# Dash.net
KiCad netlist of a schematic drawn in Altium Designer
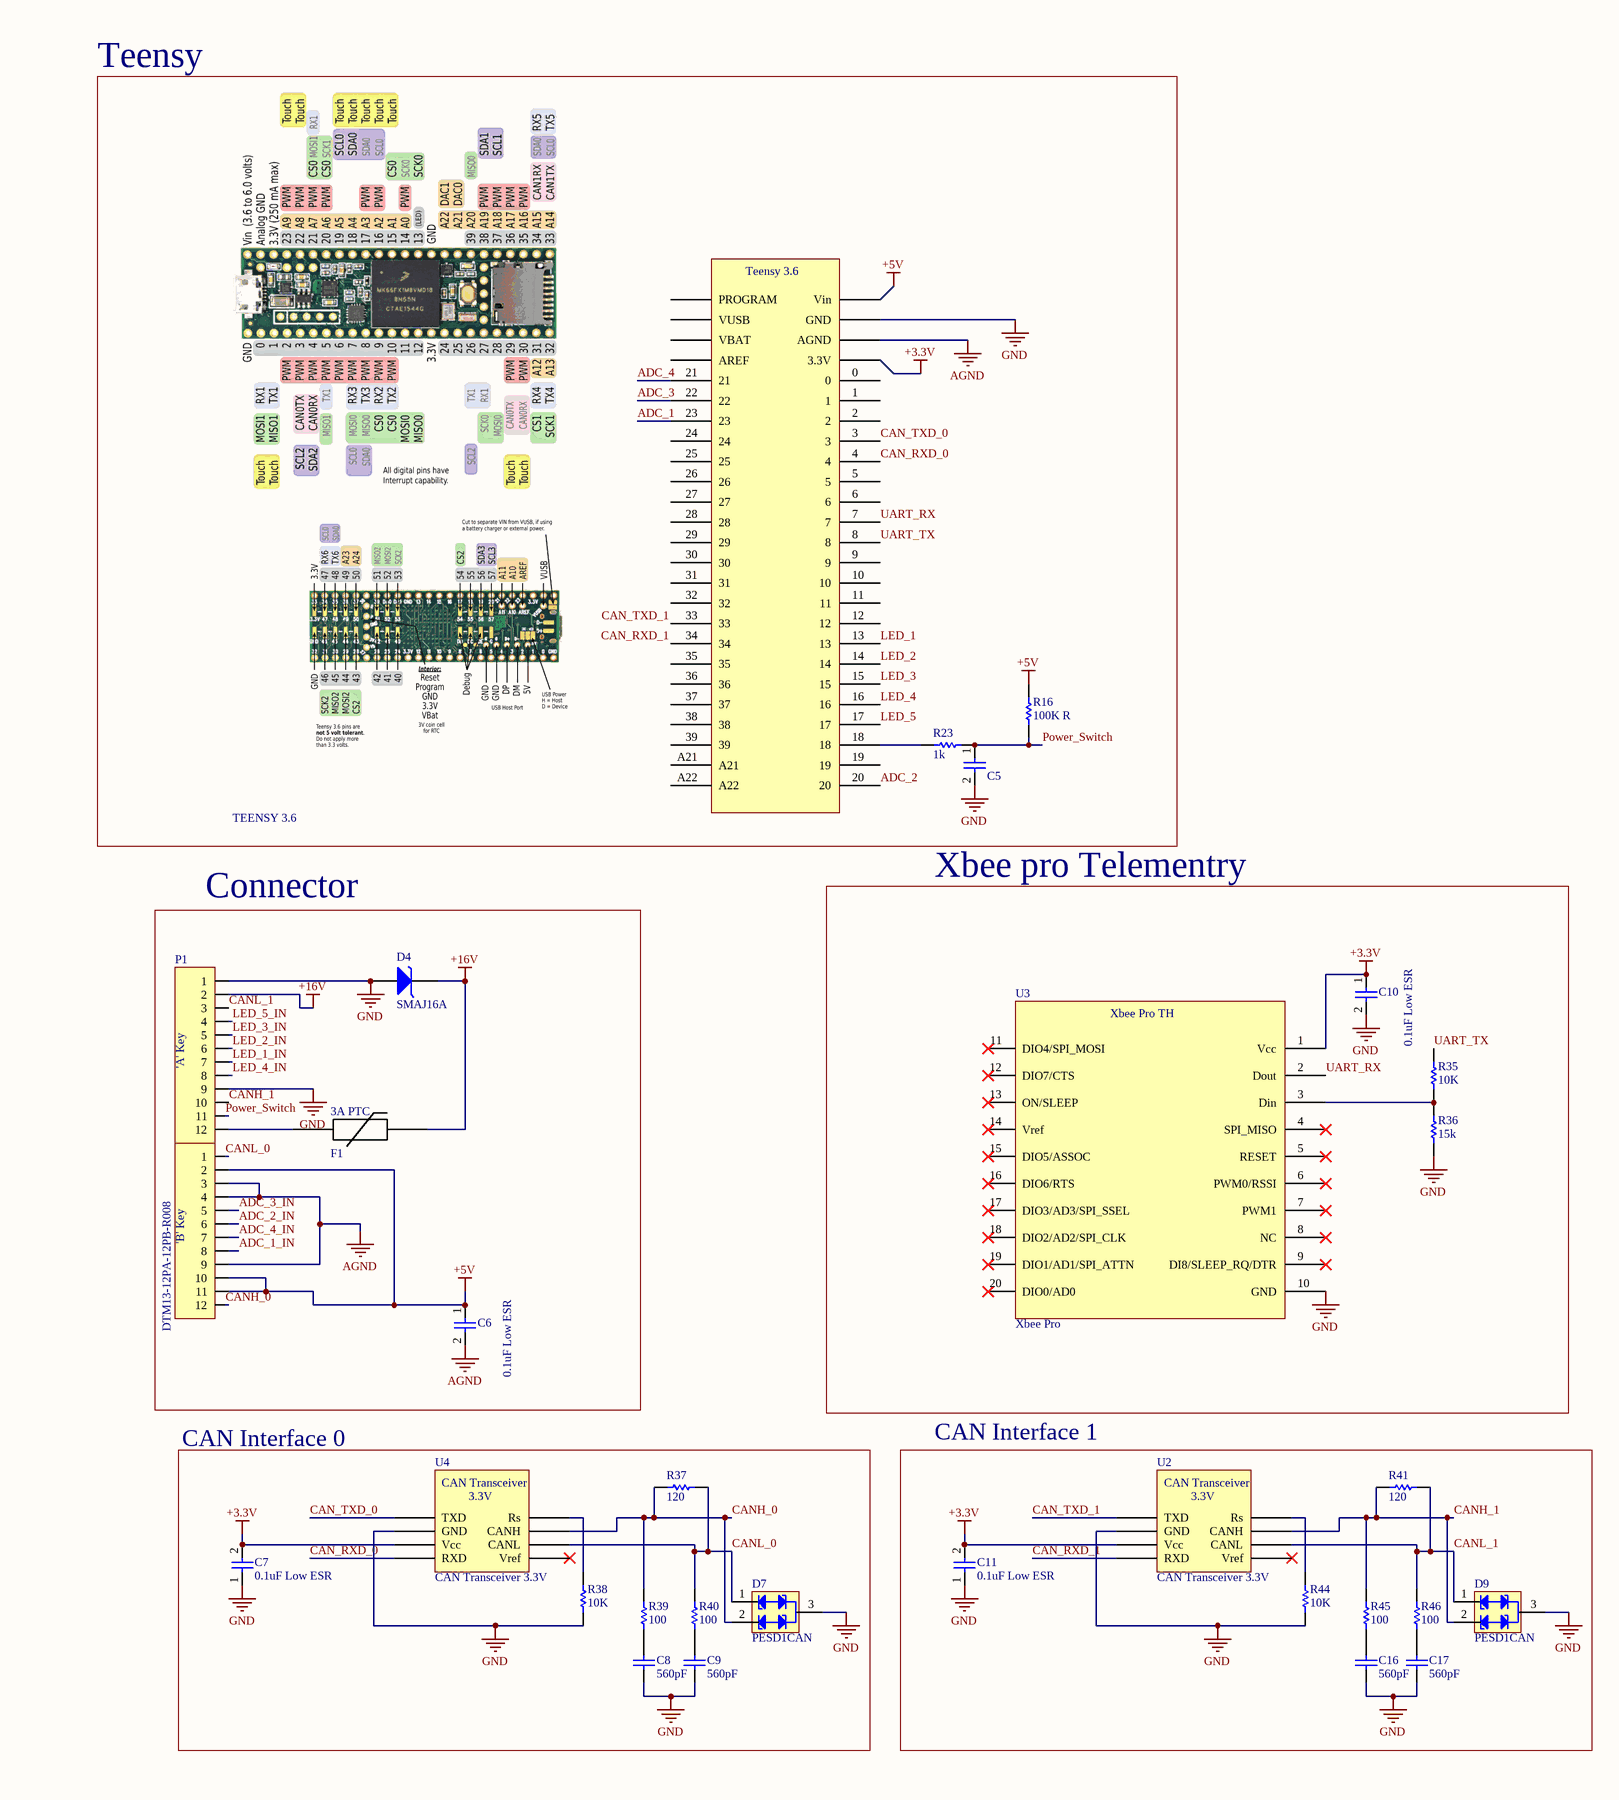
[diagram p0: Dash.SchDoc, left]
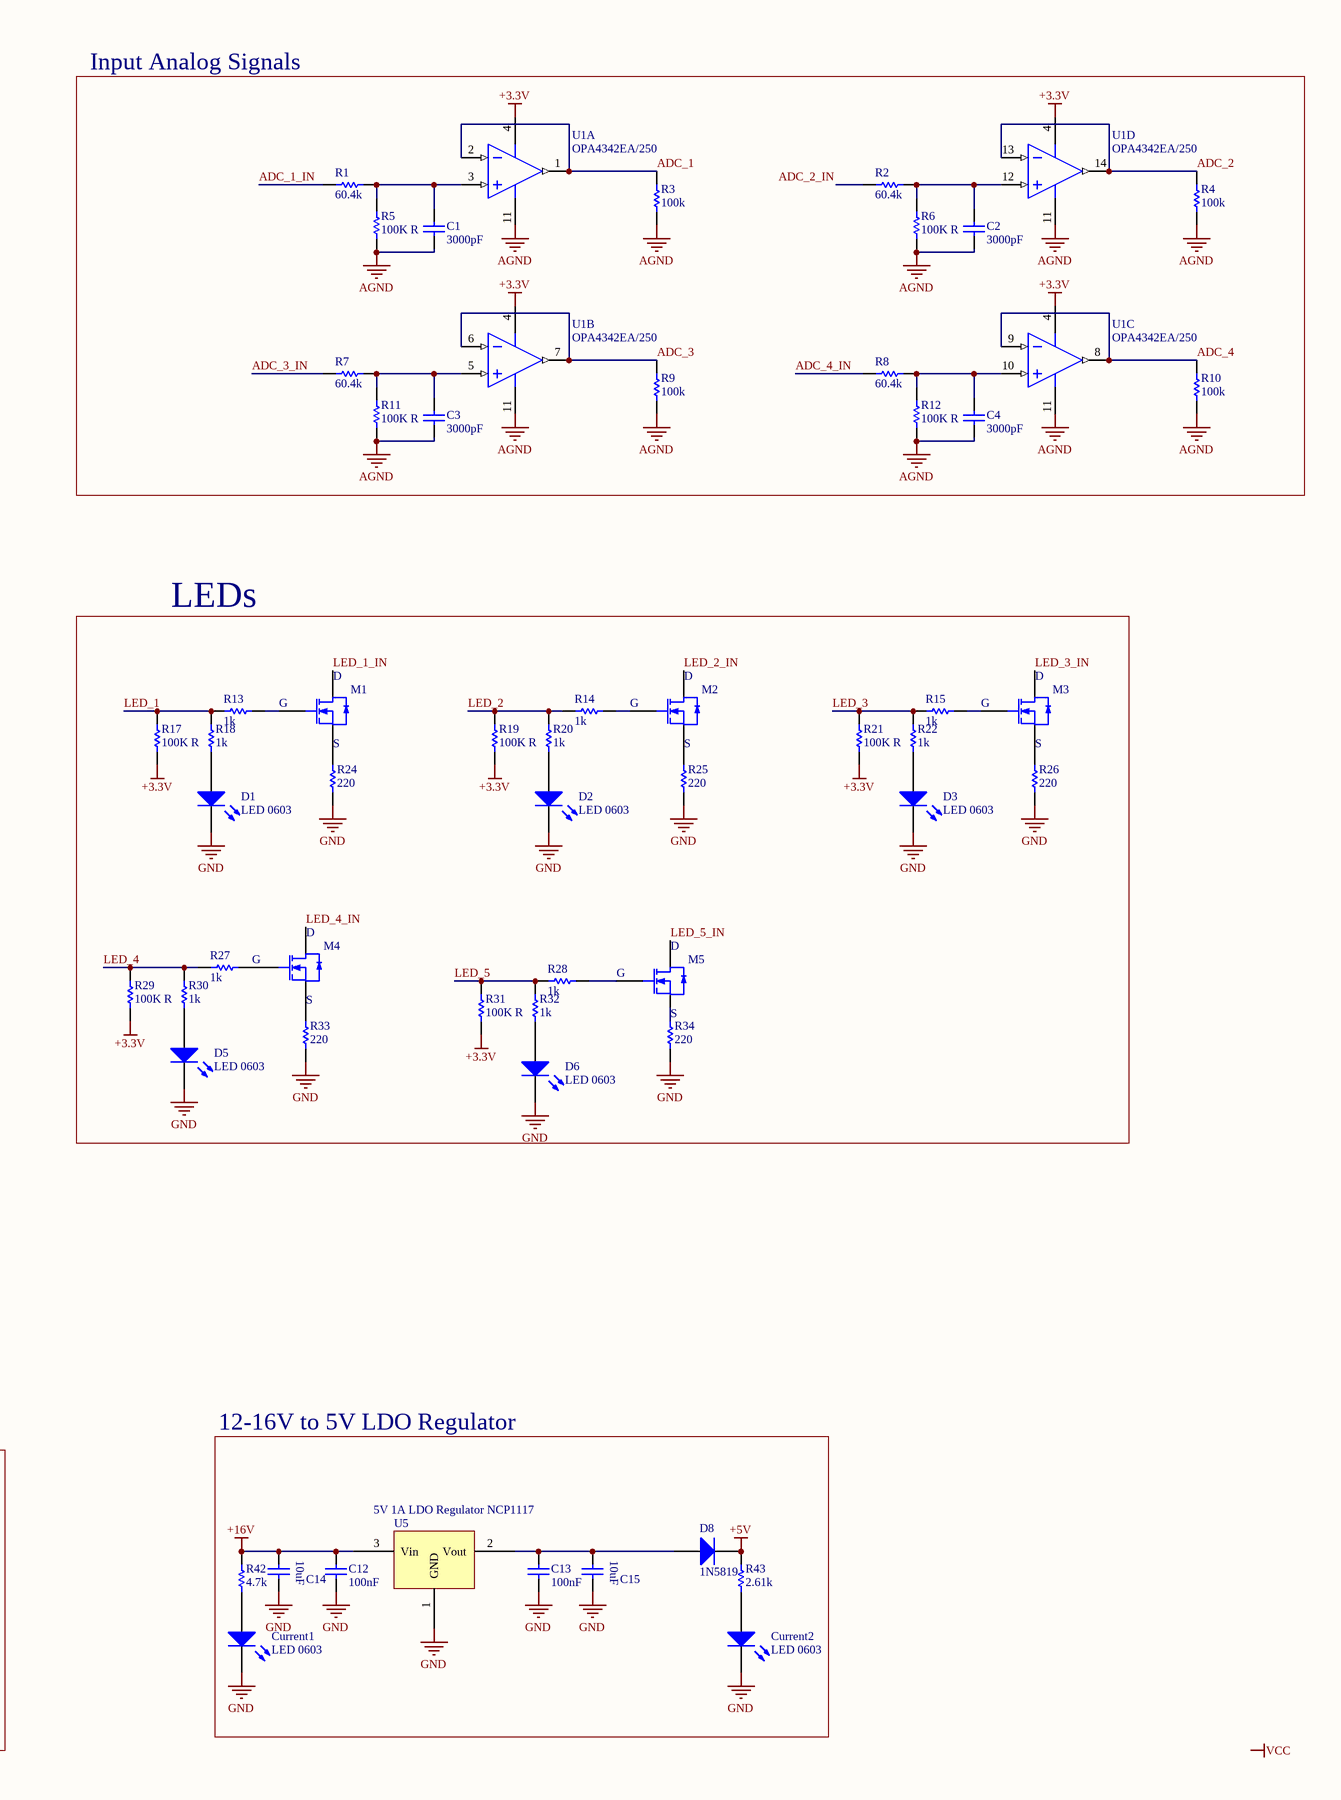
[diagram p1: Dash.SchDoc, right]

(export (version "E")
  (design (tool "Eeschema 10.0.6"))
  (components
    (comp (ref "C1")
      (value "C 3000pF")
      (footprint "DASH_PcbLib:J1-0603")
      (description "0603 Ceramic Capacitor")
      (fields
        (field (name "MANUFACTURER") "Murata Electronics North America")
        (field (name "MANUFACTURER PART NUMBER") "GRM1885C1H302JA01D")
        (field (name "CAPACITANCE") "3000pF")
      )
      (libsource (lib "BTPD_Schlib") (part "C 3000pF 0603 50V"))
    )
    (comp (ref "C2")
      (value "C 3000pF")
      (footprint "DASH_PcbLib:J1-0603")
      (description "0603 Ceramic Capacitor")
      (fields
        (field (name "MANUFACTURER") "Murata Electronics North America")
        (field (name "MANUFACTURER PART NUMBER") "GRM1885C1H302JA01D")
        (field (name "CAPACITANCE") "3000pF")
      )
      (libsource (lib "BTPD_Schlib") (part "C 3000pF 0603 50V"))
    )
    (comp (ref "C3")
      (value "C 3000pF")
      (footprint "DASH_PcbLib:J1-0603")
      (description "0603 Ceramic Capacitor")
      (fields
        (field (name "MANUFACTURER") "Murata Electronics North America")
        (field (name "MANUFACTURER PART NUMBER") "GRM1885C1H302JA01D")
        (field (name "CAPACITANCE") "3000pF")
      )
      (libsource (lib "BTPD_Schlib") (part "C 3000pF 0603 50V"))
    )
    (comp (ref "C4")
      (value "C 3000pF")
      (footprint "DASH_PcbLib:J1-0603")
      (description "0603 Ceramic Capacitor")
      (fields
        (field (name "MANUFACTURER") "Murata Electronics North America")
        (field (name "MANUFACTURER PART NUMBER") "GRM1885C1H302JA01D")
        (field (name "CAPACITANCE") "3000pF")
      )
      (libsource (lib "BTPD_Schlib") (part "C 3000pF 0603 50V"))
    )
    (comp (ref "C5")
      (value "0.1uF Low ESR")
      (footprint "J1-0603")
      (description "CAP CER 0.1UF 100V 10% X7R 0603")
      (fields
        (field (name "MANUFACTURER") "AVX Corporation")
        (field (name "MANUFACTURER PART NUMBER") "06031U101GAT2A")
      )
      (libsource (lib "Dash") (part "C0.1uF  Low ESR 0603 250V"))
    )
    (comp (ref "C6")
      (value "0.1uF Low ESR")
      (footprint "DASH_PcbLib:J1-0603")
      (description "CAP CER 0.1UF 100V 10% X7R 0603")
      (fields
        (field (name "MANUFACTURER") "AVX Corporation")
        (field (name "MANUFACTURER PART NUMBER") "06031U101GAT2A")
      )
      (libsource (lib "BTPD_Schlib") (part "C0.1uF  Low ESR 0603 250V"))
    )
    (comp (ref "C7")
      (value "0.1uF Low ESR")
      (footprint "DASH_PcbLib:J1-0603")
      (description "CAP CER 0.1UF 100V 10% X7R 0603")
      (fields
        (field (name "MANUFACTURER") "AVX Corporation")
        (field (name "MANUFACTURER PART NUMBER") "06031U101GAT2A")
      )
      (libsource (lib "BTPD_Schlib") (part "C0.1uF  Low ESR 0603 250V"))
    )
    (comp (ref "C8")
      (value "C 560pF")
      (footprint "C0805")
      (description "0805 Ceramic Capacitor")
      (fields
        (field (name "MANUFACTURER") "KEMET")
        (field (name "MANUFACTURER PART NUMBER") "C0805C561K5RACTU")
        (field (name "CAPACITANCE") "560pF")
      )
      (libsource (lib "BTPD_Schlib") (part "C 560pF 0805 50V"))
    )
    (comp (ref "C9")
      (value "C 560pF")
      (footprint "C0805")
      (description "0805 Ceramic Capacitor")
      (fields
        (field (name "MANUFACTURER") "KEMET")
        (field (name "MANUFACTURER PART NUMBER") "C0805C561K5RACTU")
        (field (name "CAPACITANCE") "560pF")
      )
      (libsource (lib "BTPD_Schlib") (part "C 560pF 0805 50V"))
    )
    (comp (ref "C10")
      (value "0.1uF Low ESR")
      (footprint "DASH_PcbLib:J1-0603")
      (description "CAP CER 0.1UF 100V 10% X7R 0603")
      (fields
        (field (name "MANUFACTURER") "AVX Corporation")
        (field (name "MANUFACTURER PART NUMBER") "06031U101GAT2A")
      )
      (libsource (lib "BTPD_Schlib") (part "C0.1uF  Low ESR 0603 250V"))
    )
    (comp (ref "C11")
      (value "0.1uF Low ESR")
      (footprint "DASH_PcbLib:J1-0603")
      (description "CAP CER 0.1UF 100V 10% X7R 0603")
      (fields
        (field (name "MANUFACTURER") "AVX Corporation")
        (field (name "MANUFACTURER PART NUMBER") "06031U101GAT2A")
      )
      (libsource (lib "BTPD_Schlib") (part "C0.1uF  Low ESR 0603 250V"))
    )
    (comp (ref "C12")
      (value "0.1uF 0603")
      (footprint "DASH_PcbLib:J1-0603")
      (description "CAP CER 0.1UF 50V X8L 0603")
      (fields
        (field (name "MANUFACTURER") "Murata")
        (field (name "MANUFACTURER PART NUMBER") "GCM188L81H104KA57D")
        (field (name "CAPACITANCE") "100nF")
      )
      (libsource (lib "BTPD_Schlib") (part "C 0.1uF 0603 50V"))
    )
    (comp (ref "C13")
      (value "0.1uF 0603")
      (footprint "DASH_PcbLib:J1-0603")
      (description "CAP CER 0.1UF 50V X8L 0603")
      (fields
        (field (name "MANUFACTURER") "Murata")
        (field (name "MANUFACTURER PART NUMBER") "GCM188L81H104KA57D")
        (field (name "CAPACITANCE") "100nF")
      )
      (libsource (lib "BTPD_Schlib") (part "C 0.1uF 0603 50V"))
    )
    (comp (ref "C14")
      (value "C 10uF 25V 0805")
      (footprint "DASH_PcbLib:C0805")
      (description "CAP CER 10UF 25V X5R 0805")
      (fields
        (field (name "MANUFACTURER") "Samsung Electro-Mechanics America, Inc.")
        (field (name "MANUFACTURER PART NUMBER") "CL21A106KAFN3NE")
      )
      (libsource (lib "BTPD_Schlib") (part "C 10uF 25V 0805"))
    )
    (comp (ref "C15")
      (value "C 10uF 25V 0805")
      (footprint "DASH_PcbLib:C0805")
      (description "CAP CER 10UF 25V X5R 0805")
      (fields
        (field (name "MANUFACTURER") "Samsung Electro-Mechanics America, Inc.")
        (field (name "MANUFACTURER PART NUMBER") "CL21A106KAFN3NE")
      )
      (libsource (lib "BTPD_Schlib") (part "C 10uF 25V 0805"))
    )
    (comp (ref "C16")
      (value "C 560pF")
      (footprint "C0805")
      (description "0805 Ceramic Capacitor")
      (fields
        (field (name "MANUFACTURER") "KEMET")
        (field (name "MANUFACTURER PART NUMBER") "C0805C561K5RACTU")
        (field (name "CAPACITANCE") "560pF")
      )
      (libsource (lib "BTPD_Schlib") (part "C 560pF 0805 50V"))
    )
    (comp (ref "C17")
      (value "C 560pF")
      (footprint "C0805")
      (description "0805 Ceramic Capacitor")
      (fields
        (field (name "MANUFACTURER") "KEMET")
        (field (name "MANUFACTURER PART NUMBER") "C0805C561K5RACTU")
        (field (name "CAPACITANCE") "560pF")
      )
      (libsource (lib "BTPD_Schlib") (part "C 560pF 0805 50V"))
    )
    (comp (ref "Current1")
      (value "LED 0603")
      (footprint "DASH_PcbLib:J1-0603 LED")
      (description "Typical INFRARED GaAs LED")
      (fields
        (field (name "MANUFACTURER") "Dialight")
        (field (name "MANUFACTURER PART NUMBER") "5988010107F")
        (field (name "PUBLISHER") "Altium Limited")
      )
      (libsource (lib "BTPD_Schlib") (part "LED 0603"))
    )
    (comp (ref "Current2")
      (value "LED 0603")
      (footprint "DASH_PcbLib:J1-0603 LED")
      (description "Typical INFRARED GaAs LED")
      (fields
        (field (name "MANUFACTURER") "Dialight")
        (field (name "MANUFACTURER PART NUMBER") "5988010107F")
        (field (name "PUBLISHER") "Altium Limited")
      )
      (libsource (lib "BTPD_Schlib") (part "LED 0603"))
    )
    (comp (ref "D1")
      (value "LED 0603")
      (footprint "DASH_PcbLib:J1-0603 LED")
      (description "Typical INFRARED GaAs LED")
      (fields
        (field (name "MANUFACTURER") "Dialight")
        (field (name "MANUFACTURER PART NUMBER") "5988010107F")
        (field (name "PUBLISHER") "Altium Limited")
      )
      (libsource (lib "BTPD_Schlib") (part "LED 0603"))
    )
    (comp (ref "D2")
      (value "LED 0603")
      (footprint "DASH_PcbLib:J1-0603 LED")
      (description "Typical INFRARED GaAs LED")
      (fields
        (field (name "MANUFACTURER") "Dialight")
        (field (name "MANUFACTURER PART NUMBER") "5988010107F")
        (field (name "PUBLISHER") "Altium Limited")
      )
      (libsource (lib "BTPD_Schlib") (part "LED 0603"))
    )
    (comp (ref "D3")
      (value "LED 0603")
      (footprint "DASH_PcbLib:J1-0603 LED")
      (description "Typical INFRARED GaAs LED")
      (fields
        (field (name "MANUFACTURER") "Dialight")
        (field (name "MANUFACTURER PART NUMBER") "5988010107F")
        (field (name "PUBLISHER") "Altium Limited")
      )
      (libsource (lib "BTPD_Schlib") (part "LED 0603"))
    )
    (comp (ref "D4")
      (value "SMAJ16A")
      (footprint "DASH_PcbLib:DO-214AC")
      (description "TVS DIODE 16VWM 26VC SMA")
      (fields (field (name "MANUFACTURER") "Littelfuse"))
      (libsource (lib "Fan Control IMD Teensy") (part "SMAJ16A"))
    )
    (comp (ref "D5")
      (value "LED 0603")
      (footprint "DASH_PcbLib:J1-0603 LED")
      (description "Typical INFRARED GaAs LED")
      (fields
        (field (name "MANUFACTURER") "Dialight")
        (field (name "MANUFACTURER PART NUMBER") "5988010107F")
        (field (name "PUBLISHER") "Altium Limited")
      )
      (libsource (lib "BTPD_Schlib") (part "LED 0603"))
    )
    (comp (ref "D6")
      (value "LED 0603")
      (footprint "DASH_PcbLib:J1-0603 LED")
      (description "Typical INFRARED GaAs LED")
      (fields
        (field (name "MANUFACTURER") "Dialight")
        (field (name "MANUFACTURER PART NUMBER") "5988010107F")
        (field (name "PUBLISHER") "Altium Limited")
      )
      (libsource (lib "BTPD_Schlib") (part "LED 0603"))
    )
    (comp (ref "D7")
      (value "PESD1CAN")
      (footprint "DASH_PcbLib:SOT323(SC-70)")
      (fields
        (field (name "MANUFACTURER") "Nexperia USA Inc.")
        (field (name "MANUFACTURER PART NUMBER") "PESD1CAN-UX")
      )
      (libsource (lib "BTPD_Schlib") (part "PESD1CAN"))
    )
    (comp (ref "D8")
      (value "1N5819")
      (footprint "SOD123")
      (description "Schottky Barrier Rectifier")
      (fields
        (field (name "MANUFACTURER") "Diodes Incorporated")
        (field (name "MANUFACTURER PART NUMBER") "1N5819HW-7-F")
      )
      (libsource (lib "BTPD_Schlib") (part "Diode 1N5819"))
    )
    (comp (ref "D9")
      (value "PESD1CAN")
      (footprint "DASH_PcbLib:SOT323(SC-70)")
      (fields
        (field (name "MANUFACTURER") "Nexperia USA Inc.")
        (field (name "MANUFACTURER PART NUMBER") "PESD1CAN-UX")
      )
      (libsource (lib "BTPD_Schlib") (part "PESD1CAN"))
    )
    (comp (ref "F1")
      (value "PTC RESET FUSE 24V 3A 2920")
      (footprint "2920 (7351 Metric)")
      (fields
        (field (name "MANUFACTURER") "Bourns Inc.")
        (field (name "MANUFACTURER PART NUMBER") "MF-LSMF300/24X-2")
      )
      (libsource (lib "BTPD_Schlib") (part "PTC RESET FUSE 24V 3A 2920"))
    )
    (comp (ref "M1")
      (value "Mosfet N-Channel 3.3V Switch")
      (footprint "SOT23_N")
      (description "MOSFET N-CH 30V 5A SOT23")
      (fields
        (field (name "MANUFACTURER") "Infineon Technologies")
        (field (name "MANUFACTURER PART NUMBER") "IRLML6244TRPBF")
      )
      (libsource (lib "BTPD_Schlib") (part "Mosfet IRLML6244TRPBFCT-ND"))
    )
    (comp (ref "M2")
      (value "Mosfet N-Channel 3.3V Switch")
      (footprint "SOT23_N")
      (description "MOSFET N-CH 30V 5A SOT23")
      (fields
        (field (name "MANUFACTURER") "Infineon Technologies")
        (field (name "MANUFACTURER PART NUMBER") "IRLML6244TRPBF")
      )
      (libsource (lib "BTPD_Schlib") (part "Mosfet IRLML6244TRPBFCT-ND"))
    )
    (comp (ref "M3")
      (value "Mosfet N-Channel 3.3V Switch")
      (footprint "SOT23_N")
      (description "MOSFET N-CH 30V 5A SOT23")
      (fields
        (field (name "MANUFACTURER") "Infineon Technologies")
        (field (name "MANUFACTURER PART NUMBER") "IRLML6244TRPBF")
      )
      (libsource (lib "BTPD_Schlib") (part "Mosfet IRLML6244TRPBFCT-ND"))
    )
    (comp (ref "M4")
      (value "Mosfet N-Channel 3.3V Switch")
      (footprint "SOT23_N")
      (description "MOSFET N-CH 30V 5A SOT23")
      (fields
        (field (name "MANUFACTURER") "Infineon Technologies")
        (field (name "MANUFACTURER PART NUMBER") "IRLML6244TRPBF")
      )
      (libsource (lib "BTPD_Schlib") (part "Mosfet IRLML6244TRPBFCT-ND"))
    )
    (comp (ref "M5")
      (value "Mosfet N-Channel 3.3V Switch")
      (footprint "SOT23_N")
      (description "MOSFET N-CH 30V 5A SOT23")
      (fields
        (field (name "MANUFACTURER") "Infineon Technologies")
        (field (name "MANUFACTURER PART NUMBER") "IRLML6244TRPBF")
      )
      (libsource (lib "BTPD_Schlib") (part "Mosfet IRLML6244TRPBFCT-ND"))
    )
    (comp (ref "P1")
      (value "DTM13-12PA-12PB-R008")
      (footprint "DTM13-12PA-12PB-R008")
      (fields
        (field (name "MANUFACTURER") "TE Connectivity Deutsch Connectors")
        (field (name "MANUFACTURER PART NUMBER") "DTM13-12PA-12PB-R008")
      )
      (libsource (lib "BTPD_Schlib") (part "DTM13-12PA-12PB-R008"))
    )
    (comp (ref "R1")
      (value "60.4K R")
      (footprint "J1-0603")
      (description "60.4k Resistor 0603")
      (fields
        (field (name "MANUFACTURER") "Yageo")
        (field (name "MANUFACTURER PART NUMBER") "RC0603FR-0760K4L")
        (field (name "RESISTANCE (OHMS)") "60.4k")
      )
      (libsource (lib "BTPD_Schlib") (part "R60.4k_0603"))
    )
    (comp (ref "R2")
      (value "60.4K R")
      (footprint "J1-0603")
      (description "60.4k Resistor 0603")
      (fields
        (field (name "MANUFACTURER") "Yageo")
        (field (name "MANUFACTURER PART NUMBER") "RC0603FR-0760K4L")
        (field (name "RESISTANCE (OHMS)") "60.4k")
      )
      (libsource (lib "BTPD_Schlib") (part "R60.4k_0603"))
    )
    (comp (ref "R3")
      (value "100K R")
      (footprint "J1-0603")
      (description "100k Resistor 0603")
      (fields
        (field (name "MANUFACTURER") "Yageo")
        (field (name "MANUFACTURER PART NUMBER") "RC0402FR-07100KL")
        (field (name "RESISTANCE (OHMS)") "100k")
      )
      (libsource (lib "BTPD_Schlib") (part "R100k_0603"))
    )
    (comp (ref "R4")
      (value "100K R")
      (footprint "J1-0603")
      (description "100k Resistor 0603")
      (fields
        (field (name "MANUFACTURER") "Yageo")
        (field (name "MANUFACTURER PART NUMBER") "RC0402FR-07100KL")
        (field (name "RESISTANCE (OHMS)") "100k")
      )
      (libsource (lib "BTPD_Schlib") (part "R100k_0603"))
    )
    (comp (ref "R5")
      (value "100K R")
      (footprint "J1-0603")
      (description "100k Resistor 0603")
      (fields
        (field (name "MANUFACTURER") "Yageo")
        (field (name "MANUFACTURER PART NUMBER") "RC0402FR-07100KL")
      )
      (libsource (lib "BTPD_Schlib") (part "R100k_0603"))
    )
    (comp (ref "R6")
      (value "100K R")
      (footprint "J1-0603")
      (description "100k Resistor 0603")
      (fields
        (field (name "MANUFACTURER") "Yageo")
        (field (name "MANUFACTURER PART NUMBER") "RC0402FR-07100KL")
      )
      (libsource (lib "BTPD_Schlib") (part "R100k_0603"))
    )
    (comp (ref "R7")
      (value "60.4K R")
      (footprint "J1-0603")
      (description "60.4k Resistor 0603")
      (fields
        (field (name "MANUFACTURER") "Yageo")
        (field (name "MANUFACTURER PART NUMBER") "RC0603FR-0760K4L")
        (field (name "RESISTANCE (OHMS)") "60.4k")
      )
      (libsource (lib "BTPD_Schlib") (part "R60.4k_0603"))
    )
    (comp (ref "R8")
      (value "60.4K R")
      (footprint "J1-0603")
      (description "60.4k Resistor 0603")
      (fields
        (field (name "MANUFACTURER") "Yageo")
        (field (name "MANUFACTURER PART NUMBER") "RC0603FR-0760K4L")
        (field (name "RESISTANCE (OHMS)") "60.4k")
      )
      (libsource (lib "BTPD_Schlib") (part "R60.4k_0603"))
    )
    (comp (ref "R9")
      (value "100K R")
      (footprint "J1-0603")
      (description "100k Resistor 0603")
      (fields
        (field (name "MANUFACTURER") "Yageo")
        (field (name "MANUFACTURER PART NUMBER") "RC0402FR-07100KL")
        (field (name "RESISTANCE (OHMS)") "100k")
      )
      (libsource (lib "BTPD_Schlib") (part "R100k_0603"))
    )
    (comp (ref "R10")
      (value "100K R")
      (footprint "J1-0603")
      (description "100k Resistor 0603")
      (fields
        (field (name "MANUFACTURER") "Yageo")
        (field (name "MANUFACTURER PART NUMBER") "RC0402FR-07100KL")
        (field (name "RESISTANCE (OHMS)") "100k")
      )
      (libsource (lib "BTPD_Schlib") (part "R100k_0603"))
    )
    (comp (ref "R11")
      (value "100K R")
      (footprint "J1-0603")
      (description "100k Resistor 0603")
      (fields
        (field (name "MANUFACTURER") "Yageo")
        (field (name "MANUFACTURER PART NUMBER") "RC0402FR-07100KL")
      )
      (libsource (lib "BTPD_Schlib") (part "R100k_0603"))
    )
    (comp (ref "R12")
      (value "100K R")
      (footprint "J1-0603")
      (description "100k Resistor 0603")
      (fields
        (field (name "MANUFACTURER") "Yageo")
        (field (name "MANUFACTURER PART NUMBER") "RC0402FR-07100KL")
      )
      (libsource (lib "BTPD_Schlib") (part "R100k_0603"))
    )
    (comp (ref "R13")
      (value "1K R")
      (footprint "J1-0603")
      (description "1k Resistor 0603")
      (fields
        (field (name "MANUFACTURER") "Yageo")
        (field (name "MANUFACTURER PART NUMBER") "RC0603FR-071KL")
        (field (name "RESISTANCE (OHMS)") "1k")
      )
      (libsource (lib "BTPD_Schlib") (part "R1k_0603"))
    )
    (comp (ref "R14")
      (value "1K R")
      (footprint "J1-0603")
      (description "1k Resistor 0603")
      (fields
        (field (name "MANUFACTURER") "Yageo")
        (field (name "MANUFACTURER PART NUMBER") "RC0603FR-071KL")
        (field (name "RESISTANCE (OHMS)") "1k")
      )
      (libsource (lib "BTPD_Schlib") (part "R1k_0603"))
    )
    (comp (ref "R15")
      (value "1K R")
      (footprint "J1-0603")
      (description "1k Resistor 0603")
      (fields
        (field (name "MANUFACTURER") "Yageo")
        (field (name "MANUFACTURER PART NUMBER") "RC0603FR-071KL")
        (field (name "RESISTANCE (OHMS)") "1k")
      )
      (libsource (lib "BTPD_Schlib") (part "R1k_0603"))
    )
    (comp (ref "R16")
      (value "100K R")
      (footprint "J1-0603")
      (description "100k Resistor 0603")
      (fields
        (field (name "MANUFACTURER") "Yageo")
        (field (name "MANUFACTURER PART NUMBER") "RC0402FR-07100KL")
      )
      (libsource (lib "Dash") (part "R100k_0603"))
    )
    (comp (ref "R17")
      (value "100K R")
      (footprint "J1-0603")
      (description "100k Resistor 0603")
      (fields
        (field (name "MANUFACTURER") "Yageo")
        (field (name "MANUFACTURER PART NUMBER") "RC0402FR-07100KL")
      )
      (libsource (lib "BTPD_Schlib") (part "R100k_0603"))
    )
    (comp (ref "R18")
      (value "1K R")
      (footprint "J1-0603")
      (description "1k Resistor 0603")
      (fields
        (field (name "MANUFACTURER") "Yageo")
        (field (name "MANUFACTURER PART NUMBER") "RC0603FR-071KL")
        (field (name "RESISTANCE (OHMS)") "1k")
      )
      (libsource (lib "BTPD_Schlib") (part "R1k_0603"))
    )
    (comp (ref "R19")
      (value "100K R")
      (footprint "J1-0603")
      (description "100k Resistor 0603")
      (fields
        (field (name "MANUFACTURER") "Yageo")
        (field (name "MANUFACTURER PART NUMBER") "RC0402FR-07100KL")
      )
      (libsource (lib "BTPD_Schlib") (part "R100k_0603"))
    )
    (comp (ref "R20")
      (value "1K R")
      (footprint "J1-0603")
      (description "1k Resistor 0603")
      (fields
        (field (name "MANUFACTURER") "Yageo")
        (field (name "MANUFACTURER PART NUMBER") "RC0603FR-071KL")
        (field (name "RESISTANCE (OHMS)") "1k")
      )
      (libsource (lib "BTPD_Schlib") (part "R1k_0603"))
    )
    (comp (ref "R21")
      (value "100K R")
      (footprint "J1-0603")
      (description "100k Resistor 0603")
      (fields
        (field (name "MANUFACTURER") "Yageo")
        (field (name "MANUFACTURER PART NUMBER") "RC0402FR-07100KL")
      )
      (libsource (lib "BTPD_Schlib") (part "R100k_0603"))
    )
    (comp (ref "R22")
      (value "1K R")
      (footprint "J1-0603")
      (description "1k Resistor 0603")
      (fields
        (field (name "MANUFACTURER") "Yageo")
        (field (name "MANUFACTURER PART NUMBER") "RC0603FR-071KL")
        (field (name "RESISTANCE (OHMS)") "1k")
      )
      (libsource (lib "BTPD_Schlib") (part "R1k_0603"))
    )
    (comp (ref "R23")
      (value "1K R")
      (footprint "J1-0603")
      (description "1k Resistor 0603")
      (fields
        (field (name "MANUFACTURER") "Yageo")
        (field (name "MANUFACTURER PART NUMBER") "RC0603FR-071KL")
        (field (name "RESISTANCE (OHMS)") "1k")
      )
      (libsource (lib "Dash") (part "R1k_0603"))
    )
    (comp (ref "R24")
      (value "220 R")
      (footprint "J1-0603")
      (description "220 Resistor 0603")
      (fields
        (field (name "MANUFACTURER") "TE Connectivity Passive Product")
        (field (name "TOLERANCE") "±1%")
        (field (name "RESISTANCE (OHMS)") "220")
      )
      (libsource (lib "Dash") (part "R220_0603"))
    )
    (comp (ref "R25")
      (value "220 R")
      (footprint "J1-0603")
      (description "220 Resistor 0603")
      (fields
        (field (name "MANUFACTURER") "TE Connectivity Passive Product")
        (field (name "TOLERANCE") "±1%")
        (field (name "RESISTANCE (OHMS)") "220")
      )
      (libsource (lib "Dash") (part "R220_0603"))
    )
    (comp (ref "R26")
      (value "220 R")
      (footprint "J1-0603")
      (description "220 Resistor 0603")
      (fields
        (field (name "MANUFACTURER") "TE Connectivity Passive Product")
        (field (name "TOLERANCE") "±1%")
        (field (name "RESISTANCE (OHMS)") "220")
      )
      (libsource (lib "Dash") (part "R220_0603"))
    )
    (comp (ref "R27")
      (value "1K R")
      (footprint "J1-0603")
      (description "1k Resistor 0603")
      (fields
        (field (name "MANUFACTURER") "Yageo")
        (field (name "MANUFACTURER PART NUMBER") "RC0603FR-071KL")
        (field (name "RESISTANCE (OHMS)") "1k")
      )
      (libsource (lib "BTPD_Schlib") (part "R1k_0603"))
    )
    (comp (ref "R28")
      (value "1K R")
      (footprint "J1-0603")
      (description "1k Resistor 0603")
      (fields
        (field (name "MANUFACTURER") "Yageo")
        (field (name "MANUFACTURER PART NUMBER") "RC0603FR-071KL")
        (field (name "RESISTANCE (OHMS)") "1k")
      )
      (libsource (lib "BTPD_Schlib") (part "R1k_0603"))
    )
    (comp (ref "R29")
      (value "100K R")
      (footprint "J1-0603")
      (description "100k Resistor 0603")
      (fields
        (field (name "MANUFACTURER") "Yageo")
        (field (name "MANUFACTURER PART NUMBER") "RC0402FR-07100KL")
      )
      (libsource (lib "BTPD_Schlib") (part "R100k_0603"))
    )
    (comp (ref "R30")
      (value "1K R")
      (footprint "J1-0603")
      (description "1k Resistor 0603")
      (fields
        (field (name "MANUFACTURER") "Yageo")
        (field (name "MANUFACTURER PART NUMBER") "RC0603FR-071KL")
        (field (name "RESISTANCE (OHMS)") "1k")
      )
      (libsource (lib "BTPD_Schlib") (part "R1k_0603"))
    )
    (comp (ref "R31")
      (value "100K R")
      (footprint "J1-0603")
      (description "100k Resistor 0603")
      (fields
        (field (name "MANUFACTURER") "Yageo")
        (field (name "MANUFACTURER PART NUMBER") "RC0402FR-07100KL")
      )
      (libsource (lib "BTPD_Schlib") (part "R100k_0603"))
    )
    (comp (ref "R32")
      (value "1K R")
      (footprint "J1-0603")
      (description "1k Resistor 0603")
      (fields
        (field (name "MANUFACTURER") "Yageo")
        (field (name "MANUFACTURER PART NUMBER") "RC0603FR-071KL")
        (field (name "RESISTANCE (OHMS)") "1k")
      )
      (libsource (lib "BTPD_Schlib") (part "R1k_0603"))
    )
    (comp (ref "R33")
      (value "220 R")
      (footprint "J1-0603")
      (description "220 Resistor 0603")
      (fields
        (field (name "MANUFACTURER") "TE Connectivity Passive Product")
        (field (name "TOLERANCE") "±1%")
        (field (name "RESISTANCE (OHMS)") "220")
      )
      (libsource (lib "Dash") (part "R220_0603"))
    )
    (comp (ref "R34")
      (value "220 R")
      (footprint "J1-0603")
      (description "220 Resistor 0603")
      (fields
        (field (name "MANUFACTURER") "TE Connectivity Passive Product")
        (field (name "TOLERANCE") "±1%")
        (field (name "RESISTANCE (OHMS)") "220")
      )
      (libsource (lib "Dash") (part "R220_0603"))
    )
    (comp (ref "R35")
      (value "10K")
      (footprint "DASH_PcbLib:0603")
      (description "10k Resistor 0603")
      (fields
        (field (name "MANUFACTURER") "Panasonic Electronic Components")
        (field (name "MANUFACTURER PART NUMBER") "ERJ-3EKF1002V")
        (field (name "PUBLISHER") "Altium Limited")
      )
      (libsource (lib "Passives") (part "R10k_0603"))
    )
    (comp (ref "R36")
      (value "15k")
      (footprint "DASH_PcbLib:0603")
      (description "15k Resistor 0603")
      (fields
        (field (name "MANUFACTURER") "Yageo")
        (field (name "MANUFACTURER PART NUMBER") "RC0603FR-0715KL")
      )
      (libsource (lib "Passives") (part "R15k_0603"))
    )
    (comp (ref "R37")
      (value "120 R")
      (footprint "J1-0603")
      (description "120 Resistor 0603")
      (fields
        (field (name "MANUFACTURER") "Yageo")
        (field (name "MANUFACTURER PART NUMBER") "RC0603FR-07120RL")
        (field (name "RESISTANCE (OHMS)") "120")
      )
      (libsource (lib "BTPD_Schlib") (part "R120_0603"))
    )
    (comp (ref "R38")
      (value "10K")
      (footprint "J1-0603")
      (description "10k Resistor 0603")
      (fields
        (field (name "MANUFACTURER") "Panasonic Electronic Components")
        (field (name "MANUFACTURER PART NUMBER") "ERJ-3EKF1002V")
        (field (name "PUBLISHER") "Altium Limited")
      )
      (libsource (lib "BTPD_Schlib") (part "R10k_0603"))
    )
    (comp (ref "R39")
      (value "100 R")
      (footprint "J1-0603")
      (description "100 Resistor 0603")
      (fields
        (field (name "MANUFACTURER") "Panasonic Electronic Components")
        (field (name "MANUFACTURER PART NUMBER") "ERJ-3EKF1000V")
        (field (name "RESISTANCE (OHMS)") "100")
      )
      (libsource (lib "BTPD_Schlib") (part "R100_0603"))
    )
    (comp (ref "R40")
      (value "100 R")
      (footprint "J1-0603")
      (description "100 Resistor 0603")
      (fields
        (field (name "MANUFACTURER") "Panasonic Electronic Components")
        (field (name "MANUFACTURER PART NUMBER") "ERJ-3EKF1000V")
        (field (name "RESISTANCE (OHMS)") "100")
      )
      (libsource (lib "BTPD_Schlib") (part "R100_0603"))
    )
    (comp (ref "R41")
      (value "120 R")
      (footprint "J1-0603")
      (description "120 Resistor 0603")
      (fields
        (field (name "MANUFACTURER") "Yageo")
        (field (name "MANUFACTURER PART NUMBER") "RC0603FR-07120RL")
        (field (name "RESISTANCE (OHMS)") "120")
      )
      (libsource (lib "BTPD_Schlib") (part "R120_0603"))
    )
    (comp (ref "R42")
      (value "4.7K R")
      (footprint "J1-0603")
      (description "4.7k Resistor 0603")
      (fields
        (field (name "MANUFACTURER") "Yageo")
        (field (name "MANUFACTURER PART NUMBER") "RC0603FR-074K7L")
        (field (name "RESISTANCE (OHMS)") "4.7k")
      )
      (libsource (lib "BTPD_Schlib") (part "R4.7k_0603"))
    )
    (comp (ref "R43")
      (value "2.61k R")
      (footprint "DASH_PcbLib:J1-0603")
      (description "2.61k Resistor 0603")
      (fields
        (field (name "MANUFACTURER") "Yageo")
        (field (name "MANUFACTURER PART NUMBER") "RC0603FR-072K61L")
        (field (name "RESISTANCE (OHMS)") "2.61k")
      )
      (libsource (lib "BTPD_Schlib") (part "R2.61k_0603"))
    )
    (comp (ref "R44")
      (value "10K")
      (footprint "J1-0603")
      (description "10k Resistor 0603")
      (fields
        (field (name "MANUFACTURER") "Panasonic Electronic Components")
        (field (name "MANUFACTURER PART NUMBER") "ERJ-3EKF1002V")
        (field (name "PUBLISHER") "Altium Limited")
      )
      (libsource (lib "BTPD_Schlib") (part "R10k_0603"))
    )
    (comp (ref "R45")
      (value "100 R")
      (footprint "J1-0603")
      (description "100 Resistor 0603")
      (fields
        (field (name "MANUFACTURER") "Panasonic Electronic Components")
        (field (name "MANUFACTURER PART NUMBER") "ERJ-3EKF1000V")
        (field (name "RESISTANCE (OHMS)") "100")
      )
      (libsource (lib "BTPD_Schlib") (part "R100_0603"))
    )
    (comp (ref "R46")
      (value "100 R")
      (footprint "J1-0603")
      (description "100 Resistor 0603")
      (fields
        (field (name "MANUFACTURER") "Panasonic Electronic Components")
        (field (name "MANUFACTURER PART NUMBER") "ERJ-3EKF1000V")
        (field (name "RESISTANCE (OHMS)") "100")
      )
      (libsource (lib "BTPD_Schlib") (part "R100_0603"))
    )
    (comp (ref "TEENSY 3.6")
      (value "Teensy 3.6")
      (footprint "DASH_PcbLib:Teensy 3.6")
      (fields (field (name "MANUFACTURER") "3M") (field (name "MANUFACTURER PART NUMBER") "929974-01-36-RK"))
      (libsource (lib "Dash") (part "Teensy 3.6"))
    )
    (comp (ref "U1")
      (value "OPA4342EA/250")
      (footprint "TSSOP-14")
      (fields (field (name "MANUFACTURER") "Texas Instruments"))
      (libsource (lib "BTPD_Schlib") (part "OPA4342EA/250"))
    )
    (comp (ref "U2")
      (value "CAN Transceiver 3.3V")
      (footprint "8-SOIC")
      (fields
        (field (name "MANUFACTURER") "Texas Instruments")
        (field (name "MANUFACTURER PART NUMBER") "SN65HVD230DR")
      )
      (libsource (lib "BTPD_Schlib") (part "CAN Transceiver 3.3V"))
    )
    (comp (ref "U3")
      (value "Xbee Pro")
      (footprint "DASH_PcbLib:Xbee Pro")
      (fields
        (field (name "MANUFACTURER") "Samtec Inc.")
        (field (name "MANUFACTURER PART NUMBER") "MMS-110-01-L-SV")
      )
      (libsource (lib "Components") (part "Xbee Pro"))
    )
    (comp (ref "U4")
      (value "CAN Transceiver 3.3V")
      (footprint "8-SOIC")
      (fields
        (field (name "MANUFACTURER") "Texas Instruments")
        (field (name "MANUFACTURER PART NUMBER") "SN65HVD230DR")
      )
      (libsource (lib "BTPD_Schlib") (part "CAN Transceiver 3.3V"))
    )
    (comp (ref "U5")
      (value "5V 1A LDO Regulator NCP1117")
      (footprint "DASH_PcbLib:SOT-223")
      (fields
        (field (name "MANUFACTURER") "ON Semiconductor")
        (field (name "MANUFACTURER PART NUMBER") "NCP1117ST50T3G")
      )
      (libsource (lib "BTPD_Schlib") (part "5V 1A LDO Regulator NCP1117"))
    )
  )
  (nets
    (net (code "1") (name "+3.3V") (class "Default")
      (node (ref "C10") (pin "1") (pinfunction "1_1") (pintype "passive"))
      (node (ref "C11") (pin "2") (pinfunction "2_2") (pintype "passive"))
      (node (ref "C7") (pin "2") (pinfunction "2_2") (pintype "passive"))
      (node (ref "R17") (pin "2") (pinfunction "2_2") (pintype "passive"))
      (node (ref "R19") (pin "2") (pinfunction "2_2") (pintype "passive"))
      (node (ref "R21") (pin "2") (pinfunction "2_2") (pintype "passive"))
      (node (ref "R29") (pin "2") (pinfunction "2_2") (pintype "passive"))
      (node (ref "R31") (pin "2") (pinfunction "2_2") (pintype "passive"))
      (node (ref "TEENSY 3.6") (pin "3.3V") (pinfunction "3.3V_3.3V") (pintype "passive"))
      (node (ref "U1") (pin "4") (pinfunction "V+_4") (pintype "power_in"))
      (node (ref "U2") (pin "3") (pinfunction "Vcc_3") (pintype "passive"))
      (node (ref "U3") (pin "1") (pinfunction "Vcc_1") (pintype "passive"))
      (node (ref "U4") (pin "3") (pinfunction "Vcc_3") (pintype "passive"))
    )
    (net (code "2") (name "+5V") (class "Default")
      (node (ref "C6") (pin "1") (pinfunction "1_1") (pintype "passive"))
      (node (ref "D8") (pin "1") (pinfunction "1_1") (pintype "passive"))
      (node (ref "P1") (pin "14") (pinfunction "2_14") (pintype "passive"))
      (node (ref "P1") (pin "22") (pinfunction "10_22") (pintype "passive"))
      (node (ref "P1") (pin "23") (pinfunction "11_23") (pintype "passive"))
      (node (ref "R16") (pin "1") (pinfunction "1_1") (pintype "passive"))
      (node (ref "R43") (pin "1") (pinfunction "1_1") (pintype "passive"))
      (node (ref "TEENSY 3.6") (pin "VIN") (pinfunction "Vin_VIN") (pintype "passive"))
    )
    (net (code "3") (name "+16V") (class "Default")
      (node (ref "C12") (pin "2") (pinfunction "2_2") (pintype "passive"))
      (node (ref "C14") (pin "1") (pinfunction "1_1") (pintype "passive"))
      (node (ref "D4") (pin "1") (pinfunction "K_1") (pintype "passive"))
      (node (ref "F1") (pin "1") (pinfunction "1_1") (pintype "passive"))
      (node (ref "P1") (pin "2") (pinfunction "2_2") (pintype "open_collector"))
      (node (ref "R42") (pin "1") (pinfunction "1_1") (pintype "passive"))
      (node (ref "U5") (pin "3") (pinfunction "Vin_3") (pintype "passive"))
    )
    (net (code "4") (name "/ADC_1") (class "Default")
      (node (ref "R3") (pin "2") (pinfunction "2_2") (pintype "passive"))
      (node (ref "TEENSY 3.6") (pin "23") (pinfunction "23_23") (pintype "passive"))
      (node (ref "U1") (pin "1") (pinfunction "OUT_A_1") (pintype "output"))
      (node (ref "U1") (pin "2") (pinfunction "IN_A-_2") (pintype "input"))
    )
    (net (code "5") (name "/ADC_1_IN") (class "Default")
      (node (ref "P1") (pin "20") (pinfunction "8_20") (pintype "passive"))
      (node (ref "R1") (pin "1") (pinfunction "1_1") (pintype "passive"))
    )
    (net (code "6") (name "/ADC_2") (class "Default")
      (node (ref "R4") (pin "2") (pinfunction "2_2") (pintype "passive"))
      (node (ref "TEENSY 3.6") (pin "20") (pinfunction "20_20") (pintype "passive"))
      (node (ref "U1") (pin "13") (pinfunction "IN_D-_13") (pintype "input"))
      (node (ref "U1") (pin "14") (pinfunction "OUT_D_14") (pintype "output"))
    )
    (net (code "7") (name "/ADC_2_IN") (class "Default")
      (node (ref "P1") (pin "18") (pinfunction "6_18") (pintype "passive"))
      (node (ref "R2") (pin "1") (pinfunction "1_1") (pintype "passive"))
    )
    (net (code "8") (name "/ADC_3") (class "Default")
      (node (ref "R9") (pin "2") (pinfunction "2_2") (pintype "passive"))
      (node (ref "TEENSY 3.6") (pin "22") (pinfunction "22_22") (pintype "passive"))
      (node (ref "U1") (pin "6") (pinfunction "IN_B-_6") (pintype "input"))
      (node (ref "U1") (pin "7") (pinfunction "OUT_B_7") (pintype "output"))
    )
    (net (code "9") (name "/ADC_3_IN") (class "Default")
      (node (ref "P1") (pin "17") (pinfunction "5_17") (pintype "passive"))
      (node (ref "R7") (pin "1") (pinfunction "1_1") (pintype "passive"))
    )
    (net (code "10") (name "/ADC_4") (class "Default")
      (node (ref "R10") (pin "2") (pinfunction "2_2") (pintype "passive"))
      (node (ref "TEENSY 3.6") (pin "21") (pinfunction "21_21") (pintype "passive"))
      (node (ref "U1") (pin "8") (pinfunction "OUT_C_8") (pintype "output"))
      (node (ref "U1") (pin "9") (pinfunction "IN_C-_9") (pintype "input"))
    )
    (net (code "11") (name "/ADC_4_IN") (class "Default")
      (node (ref "P1") (pin "19") (pinfunction "7_19") (pintype "passive"))
      (node (ref "R8") (pin "1") (pinfunction "1_1") (pintype "passive"))
    )
    (net (code "12") (name "/CANH_0") (class "Default")
      (node (ref "D7") (pin "2") (pinfunction "2_2") (pintype "passive"))
      (node (ref "P1") (pin "24") (pinfunction "12_24") (pintype "passive"))
      (node (ref "R37") (pin "1") (pinfunction "1_1") (pintype "passive"))
      (node (ref "R39") (pin "1") (pinfunction "1_1") (pintype "passive"))
      (node (ref "U4") (pin "7") (pinfunction "CANH_7") (pintype "passive"))
    )
    (net (code "13") (name "/CANH_1") (class "Default")
      (node (ref "D9") (pin "2") (pinfunction "2_2") (pintype "passive"))
      (node (ref "P1") (pin "10") (pinfunction "10_10") (pintype "passive"))
      (node (ref "R41") (pin "1") (pinfunction "1_1") (pintype "passive"))
      (node (ref "R45") (pin "1") (pinfunction "1_1") (pintype "passive"))
      (node (ref "U2") (pin "7") (pinfunction "CANH_7") (pintype "passive"))
    )
    (net (code "14") (name "/CANL_0") (class "Default")
      (node (ref "D7") (pin "1") (pinfunction "1_1") (pintype "passive"))
      (node (ref "P1") (pin "13") (pinfunction "1_13") (pintype "passive"))
      (node (ref "R37") (pin "2") (pinfunction "2_2") (pintype "passive"))
      (node (ref "R40") (pin "2") (pinfunction "2_2") (pintype "passive"))
      (node (ref "U4") (pin "6") (pinfunction "CANL_6") (pintype "passive"))
    )
    (net (code "15") (name "/CANL_1") (class "Default")
      (node (ref "D9") (pin "1") (pinfunction "1_1") (pintype "passive"))
      (node (ref "P1") (pin "3") (pinfunction "3_3") (pintype "open_collector"))
      (node (ref "R41") (pin "2") (pinfunction "2_2") (pintype "passive"))
      (node (ref "R46") (pin "2") (pinfunction "2_2") (pintype "passive"))
      (node (ref "U2") (pin "6") (pinfunction "CANL_6") (pintype "passive"))
    )
    (net (code "16") (name "/CAN_RXD_0") (class "Default")
      (node (ref "TEENSY 3.6") (pin "4") (pinfunction "4_4") (pintype "passive"))
      (node (ref "U4") (pin "4") (pinfunction "RXD_4") (pintype "passive"))
    )
    (net (code "17") (name "/CAN_RXD_1") (class "Default")
      (node (ref "TEENSY 3.6") (pin "34") (pinfunction "34_34") (pintype "passive"))
      (node (ref "U2") (pin "4") (pinfunction "RXD_4") (pintype "passive"))
    )
    (net (code "18") (name "/CAN_TXD_0") (class "Default")
      (node (ref "TEENSY 3.6") (pin "3") (pinfunction "3_3") (pintype "passive"))
      (node (ref "U4") (pin "1") (pinfunction "TXD_1") (pintype "passive"))
    )
    (net (code "19") (name "/CAN_TXD_1") (class "Default")
      (node (ref "TEENSY 3.6") (pin "33") (pinfunction "33_33") (pintype "passive"))
      (node (ref "U2") (pin "1") (pinfunction "TXD_1") (pintype "passive"))
    )
    (net (code "20") (name "/LED_1") (class "Default")
      (node (ref "R13") (pin "1") (pinfunction "1_1") (pintype "passive"))
      (node (ref "R17") (pin "1") (pinfunction "1_1") (pintype "passive"))
      (node (ref "R18") (pin "2") (pinfunction "2_2") (pintype "passive"))
      (node (ref "TEENSY 3.6") (pin "13") (pinfunction "13_13") (pintype "passive"))
    )
    (net (code "21") (name "/LED_1_IN") (class "Default")
      (node (ref "M1") (pin "1") (pinfunction "D_1") (pintype "passive"))
      (node (ref "P1") (pin "7") (pinfunction "7_7") (pintype "passive"))
    )
    (net (code "22") (name "/LED_2") (class "Default")
      (node (ref "R14") (pin "1") (pinfunction "1_1") (pintype "passive"))
      (node (ref "R19") (pin "1") (pinfunction "1_1") (pintype "passive"))
      (node (ref "R20") (pin "2") (pinfunction "2_2") (pintype "passive"))
      (node (ref "TEENSY 3.6") (pin "14") (pinfunction "14_14") (pintype "passive"))
    )
    (net (code "23") (name "/LED_2_IN") (class "Default")
      (node (ref "M2") (pin "1") (pinfunction "D_1") (pintype "passive"))
      (node (ref "P1") (pin "6") (pinfunction "6_6") (pintype "passive"))
    )
    (net (code "24") (name "/LED_3") (class "Default")
      (node (ref "R15") (pin "1") (pinfunction "1_1") (pintype "passive"))
      (node (ref "R21") (pin "1") (pinfunction "1_1") (pintype "passive"))
      (node (ref "R22") (pin "2") (pinfunction "2_2") (pintype "passive"))
      (node (ref "TEENSY 3.6") (pin "15") (pinfunction "15_15") (pintype "passive"))
    )
    (net (code "25") (name "/LED_3_IN") (class "Default")
      (node (ref "M3") (pin "1") (pinfunction "D_1") (pintype "passive"))
      (node (ref "P1") (pin "5") (pinfunction "5_5") (pintype "open_collector"))
    )
    (net (code "26") (name "/LED_4") (class "Default")
      (node (ref "R27") (pin "1") (pinfunction "1_1") (pintype "passive"))
      (node (ref "R29") (pin "1") (pinfunction "1_1") (pintype "passive"))
      (node (ref "R30") (pin "2") (pinfunction "2_2") (pintype "passive"))
      (node (ref "TEENSY 3.6") (pin "16") (pinfunction "16_16") (pintype "passive"))
    )
    (net (code "27") (name "/LED_4_IN") (class "Default")
      (node (ref "M4") (pin "1") (pinfunction "D_1") (pintype "passive"))
      (node (ref "P1") (pin "8") (pinfunction "8_8") (pintype "passive"))
    )
    (net (code "28") (name "/LED_5") (class "Default")
      (node (ref "R28") (pin "1") (pinfunction "1_1") (pintype "passive"))
      (node (ref "R31") (pin "1") (pinfunction "1_1") (pintype "passive"))
      (node (ref "R32") (pin "2") (pinfunction "2_2") (pintype "passive"))
      (node (ref "TEENSY 3.6") (pin "17") (pinfunction "17_17") (pintype "passive"))
    )
    (net (code "29") (name "/LED_5_IN") (class "Default")
      (node (ref "M5") (pin "1") (pinfunction "D_1") (pintype "passive"))
      (node (ref "P1") (pin "4") (pinfunction "4_4") (pintype "open_collector"))
    )
    (net (code "30") (name "/Power_Switch") (class "Default")
      (node (ref "C5") (pin "1") (pinfunction "1_1") (pintype "passive"))
      (node (ref "P1") (pin "11") (pinfunction "11_11") (pintype "passive"))
      (node (ref "R16") (pin "2") (pinfunction "2_2") (pintype "passive"))
      (node (ref "R23") (pin "2") (pinfunction "2_2") (pintype "passive"))
    )
    (net (code "31") (name "/UART_RX") (class "Default")
      (node (ref "TEENSY 3.6") (pin "7") (pinfunction "7_7") (pintype "passive"))
      (node (ref "U3") (pin "2") (pinfunction "Dout_2") (pintype "passive"))
    )
    (net (code "32") (name "/UART_TX") (class "Default")
      (node (ref "R35") (pin "2") (pinfunction "2_2") (pintype "passive"))
      (node (ref "TEENSY 3.6") (pin "8") (pinfunction "8_8") (pintype "passive"))
    )
    (net (code "33") (name "AGND") (class "Default")
      (node (ref "C1") (pin "2") (pinfunction "2_2") (pintype "passive"))
      (node (ref "C2") (pin "2") (pinfunction "2_2") (pintype "passive"))
      (node (ref "C3") (pin "2") (pinfunction "2_2") (pintype "passive"))
      (node (ref "C4") (pin "2") (pinfunction "2_2") (pintype "passive"))
      (node (ref "C6") (pin "2") (pinfunction "2_2") (pintype "passive"))
      (node (ref "P1") (pin "15") (pinfunction "3_15") (pintype "passive"))
      (node (ref "P1") (pin "16") (pinfunction "4_16") (pintype "passive"))
      (node (ref "P1") (pin "21") (pinfunction "9_21") (pintype "passive"))
      (node (ref "R10") (pin "1") (pinfunction "1_1") (pintype "passive"))
      (node (ref "R11") (pin "2") (pinfunction "2_2") (pintype "passive"))
      (node (ref "R12") (pin "2") (pinfunction "2_2") (pintype "passive"))
      (node (ref "R3") (pin "1") (pinfunction "1_1") (pintype "passive"))
      (node (ref "R4") (pin "1") (pinfunction "1_1") (pintype "passive"))
      (node (ref "R5") (pin "2") (pinfunction "2_2") (pintype "passive"))
      (node (ref "R6") (pin "2") (pinfunction "2_2") (pintype "passive"))
      (node (ref "R9") (pin "1") (pinfunction "1_1") (pintype "passive"))
      (node (ref "TEENSY 3.6") (pin "AGND") (pinfunction "AGND_AGND") (pintype "passive"))
      (node (ref "U1") (pin "11") (pinfunction "V-_11") (pintype "power_in"))
    )
    (net (code "34") (name "GND") (class "Default")
      (node (ref "C10") (pin "2") (pinfunction "2_2") (pintype "passive"))
      (node (ref "C11") (pin "1") (pinfunction "1_1") (pintype "passive"))
      (node (ref "C12") (pin "1") (pinfunction "1_1") (pintype "passive"))
      (node (ref "C13") (pin "1") (pinfunction "1_1") (pintype "passive"))
      (node (ref "C14") (pin "2") (pinfunction "2_2") (pintype "passive"))
      (node (ref "C15") (pin "2") (pinfunction "2_2") (pintype "passive"))
      (node (ref "C16") (pin "1") (pinfunction "1_1") (pintype "passive"))
      (node (ref "C17") (pin "1") (pinfunction "1_1") (pintype "passive"))
      (node (ref "C5") (pin "2") (pinfunction "2_2") (pintype "passive"))
      (node (ref "C7") (pin "1") (pinfunction "1_1") (pintype "passive"))
      (node (ref "C8") (pin "1") (pinfunction "1_1") (pintype "passive"))
      (node (ref "C9") (pin "1") (pinfunction "1_1") (pintype "passive"))
      (node (ref "Current1") (pin "2") (pinfunction "K_2") (pintype "passive"))
      (node (ref "Current2") (pin "2") (pinfunction "K_2") (pintype "passive"))
      (node (ref "D1") (pin "2") (pinfunction "K_2") (pintype "passive"))
      (node (ref "D2") (pin "2") (pinfunction "K_2") (pintype "passive"))
      (node (ref "D3") (pin "2") (pinfunction "K_2") (pintype "passive"))
      (node (ref "D4") (pin "2") (pinfunction "A_2") (pintype "passive"))
      (node (ref "D5") (pin "2") (pinfunction "K_2") (pintype "passive"))
      (node (ref "D6") (pin "2") (pinfunction "K_2") (pintype "passive"))
      (node (ref "D7") (pin "3") (pinfunction "3_3") (pintype "passive"))
      (node (ref "D9") (pin "3") (pinfunction "3_3") (pintype "passive"))
      (node (ref "P1") (pin "1") (pinfunction "1_1") (pintype "open_collector"))
      (node (ref "P1") (pin "9") (pinfunction "9_9") (pintype "passive"))
      (node (ref "R24") (pin "2") (pinfunction "2_2") (pintype "passive"))
      (node (ref "R25") (pin "2") (pinfunction "2_2") (pintype "passive"))
      (node (ref "R26") (pin "2") (pinfunction "2_2") (pintype "passive"))
      (node (ref "R33") (pin "2") (pinfunction "2_2") (pintype "passive"))
      (node (ref "R34") (pin "2") (pinfunction "2_2") (pintype "passive"))
      (node (ref "R36") (pin "1") (pinfunction "1_1") (pintype "passive"))
      (node (ref "R38") (pin "1") (pinfunction "1_1") (pintype "passive"))
      (node (ref "R44") (pin "1") (pinfunction "1_1") (pintype "passive"))
      (node (ref "TEENSY 3.6") (pin "GND") (pinfunction "GND_GND") (pintype "passive"))
      (node (ref "U2") (pin "2") (pinfunction "GND_2") (pintype "passive"))
      (node (ref "U3") (pin "10") (pinfunction "GND_10") (pintype "passive"))
      (node (ref "U4") (pin "2") (pinfunction "GND_2") (pintype "passive"))
      (node (ref "U5") (pin "1") (pinfunction "GND_1") (pintype "passive"))
    )
    (net (code "35") (name "Net-(C8-Pad2)") (class "Default")
      (node (ref "C8") (pin "2") (pinfunction "2_2") (pintype "passive"))
      (node (ref "R39") (pin "2") (pinfunction "2_2") (pintype "passive"))
    )
    (net (code "36") (name "Net-(C9-Pad2)") (class "Default")
      (node (ref "C9") (pin "2") (pinfunction "2_2") (pintype "passive"))
      (node (ref "R40") (pin "1") (pinfunction "1_1") (pintype "passive"))
    )
    (net (code "37") (name "Net-(C16-Pad2)") (class "Default")
      (node (ref "C16") (pin "2") (pinfunction "2_2") (pintype "passive"))
      (node (ref "R45") (pin "2") (pinfunction "2_2") (pintype "passive"))
    )
    (net (code "38") (name "Net-(C17-Pad2)") (class "Default")
      (node (ref "C17") (pin "2") (pinfunction "2_2") (pintype "passive"))
      (node (ref "R46") (pin "1") (pinfunction "1_1") (pintype "passive"))
    )
    (net (code "39") (name "Net-(Current1-A)") (class "Default")
      (node (ref "Current1") (pin "1") (pinfunction "A_1") (pintype "passive"))
      (node (ref "R42") (pin "2") (pinfunction "2_2") (pintype "passive"))
    )
    (net (code "40") (name "Net-(Current2-A)") (class "Default")
      (node (ref "Current2") (pin "1") (pinfunction "A_1") (pintype "passive"))
      (node (ref "R43") (pin "2") (pinfunction "2_2") (pintype "passive"))
    )
    (net (code "41") (name "Net-(D1-A)") (class "Default")
      (node (ref "D1") (pin "1") (pinfunction "A_1") (pintype "passive"))
      (node (ref "R18") (pin "1") (pinfunction "1_1") (pintype "passive"))
    )
    (net (code "42") (name "Net-(D2-A)") (class "Default")
      (node (ref "D2") (pin "1") (pinfunction "A_1") (pintype "passive"))
      (node (ref "R20") (pin "1") (pinfunction "1_1") (pintype "passive"))
    )
    (net (code "43") (name "Net-(D3-A)") (class "Default")
      (node (ref "D3") (pin "1") (pinfunction "A_1") (pintype "passive"))
      (node (ref "R22") (pin "1") (pinfunction "1_1") (pintype "passive"))
    )
    (net (code "44") (name "Net-(D5-A)") (class "Default")
      (node (ref "D5") (pin "1") (pinfunction "A_1") (pintype "passive"))
      (node (ref "R30") (pin "1") (pinfunction "1_1") (pintype "passive"))
    )
    (net (code "45") (name "Net-(D6-A)") (class "Default")
      (node (ref "D6") (pin "1") (pinfunction "A_1") (pintype "passive"))
      (node (ref "R32") (pin "1") (pinfunction "1_1") (pintype "passive"))
    )
    (net (code "46") (name "Net-(F1-Pad2)") (class "Default")
      (node (ref "F1") (pin "2") (pinfunction "2_2") (pintype "passive"))
      (node (ref "P1") (pin "12") (pinfunction "12_12") (pintype "passive"))
    )
    (net (code "47") (name "Net-(M1-G)") (class "Default")
      (node (ref "M1") (pin "3") (pinfunction "G_3") (pintype "passive"))
      (node (ref "R13") (pin "2") (pinfunction "2_2") (pintype "passive"))
    )
    (net (code "48") (name "Net-(M1-S)") (class "Default")
      (node (ref "M1") (pin "2") (pinfunction "S_2") (pintype "passive"))
      (node (ref "R24") (pin "1") (pinfunction "1_1") (pintype "passive"))
    )
    (net (code "49") (name "Net-(M2-G)") (class "Default")
      (node (ref "M2") (pin "3") (pinfunction "G_3") (pintype "passive"))
      (node (ref "R14") (pin "2") (pinfunction "2_2") (pintype "passive"))
    )
    (net (code "50") (name "Net-(M2-S)") (class "Default")
      (node (ref "M2") (pin "2") (pinfunction "S_2") (pintype "passive"))
      (node (ref "R25") (pin "1") (pinfunction "1_1") (pintype "passive"))
    )
    (net (code "51") (name "Net-(M3-G)") (class "Default")
      (node (ref "M3") (pin "3") (pinfunction "G_3") (pintype "passive"))
      (node (ref "R15") (pin "2") (pinfunction "2_2") (pintype "passive"))
    )
    (net (code "52") (name "Net-(M3-S)") (class "Default")
      (node (ref "M3") (pin "2") (pinfunction "S_2") (pintype "passive"))
      (node (ref "R26") (pin "1") (pinfunction "1_1") (pintype "passive"))
    )
    (net (code "53") (name "Net-(M4-G)") (class "Default")
      (node (ref "M4") (pin "3") (pinfunction "G_3") (pintype "passive"))
      (node (ref "R27") (pin "2") (pinfunction "2_2") (pintype "passive"))
    )
    (net (code "54") (name "Net-(M4-S)") (class "Default")
      (node (ref "M4") (pin "2") (pinfunction "S_2") (pintype "passive"))
      (node (ref "R33") (pin "1") (pinfunction "1_1") (pintype "passive"))
    )
    (net (code "55") (name "Net-(M5-G)") (class "Default")
      (node (ref "M5") (pin "3") (pinfunction "G_3") (pintype "passive"))
      (node (ref "R28") (pin "2") (pinfunction "2_2") (pintype "passive"))
    )
    (net (code "56") (name "Net-(M5-S)") (class "Default")
      (node (ref "M5") (pin "2") (pinfunction "S_2") (pintype "passive"))
      (node (ref "R34") (pin "1") (pinfunction "1_1") (pintype "passive"))
    )
    (net (code "57") (name "Net-(R23-Pad1)") (class "Default")
      (node (ref "R23") (pin "1") (pinfunction "1_1") (pintype "passive"))
      (node (ref "TEENSY 3.6") (pin "18") (pinfunction "18_18") (pintype "passive"))
    )
    (net (code "58") (name "Net-(U1A-IN_A+)") (class "Default")
      (node (ref "C1") (pin "1") (pinfunction "1_1") (pintype "passive"))
      (node (ref "R1") (pin "2") (pinfunction "2_2") (pintype "passive"))
      (node (ref "R5") (pin "1") (pinfunction "1_1") (pintype "passive"))
      (node (ref "U1") (pin "3") (pinfunction "IN_A+_3") (pintype "input"))
    )
    (net (code "59") (name "Net-(U1B-IN_B+)") (class "Default")
      (node (ref "C3") (pin "1") (pinfunction "1_1") (pintype "passive"))
      (node (ref "R11") (pin "1") (pinfunction "1_1") (pintype "passive"))
      (node (ref "R7") (pin "2") (pinfunction "2_2") (pintype "passive"))
      (node (ref "U1") (pin "5") (pinfunction "IN_B+_5") (pintype "input"))
    )
    (net (code "60") (name "Net-(U1C-IN_C+)") (class "Default")
      (node (ref "C4") (pin "1") (pinfunction "1_1") (pintype "passive"))
      (node (ref "R12") (pin "1") (pinfunction "1_1") (pintype "passive"))
      (node (ref "R8") (pin "2") (pinfunction "2_2") (pintype "passive"))
      (node (ref "U1") (pin "10") (pinfunction "IN_C+_10") (pintype "input"))
    )
    (net (code "61") (name "Net-(U1D-IN_D+)") (class "Default")
      (node (ref "C2") (pin "1") (pinfunction "1_1") (pintype "passive"))
      (node (ref "R2") (pin "2") (pinfunction "2_2") (pintype "passive"))
      (node (ref "R6") (pin "1") (pinfunction "1_1") (pintype "passive"))
      (node (ref "U1") (pin "12") (pinfunction "IN_D+_12") (pintype "input"))
    )
    (net (code "62") (name "Net-(U2-Rs)") (class "Default")
      (node (ref "R44") (pin "2") (pinfunction "2_2") (pintype "passive"))
      (node (ref "U2") (pin "8") (pinfunction "Rs_8") (pintype "passive"))
    )
    (net (code "63") (name "Net-(U3-Din)") (class "Default")
      (node (ref "R35") (pin "1") (pinfunction "1_1") (pintype "passive"))
      (node (ref "R36") (pin "2") (pinfunction "2_2") (pintype "passive"))
      (node (ref "U3") (pin "3") (pinfunction "Din_3") (pintype "passive"))
    )
    (net (code "64") (name "Net-(U4-Rs)") (class "Default")
      (node (ref "R38") (pin "2") (pinfunction "2_2") (pintype "passive"))
      (node (ref "U4") (pin "8") (pinfunction "Rs_8") (pintype "passive"))
    )
    (net (code "65") (name "Net-(U5-Vout)") (class "Default")
      (node (ref "C13") (pin "2") (pinfunction "2_2") (pintype "passive"))
      (node (ref "C15") (pin "1") (pinfunction "1_1") (pintype "passive"))
      (node (ref "D8") (pin "2") (pinfunction "2_2") (pintype "passive"))
      (node (ref "U5") (pin "2") (pinfunction "Vout_2") (pintype "passive"))
    )
    (net (code "67") (name "unconnected-(TEENSY 3.6-Pad0)") (class "Default")
      (node (ref "TEENSY 3.6") (pin "0") (pinfunction "0_0") (pintype "passive"))
    )
    (net (code "68") (name "unconnected-(TEENSY 3.6-Pad1)") (class "Default")
      (node (ref "TEENSY 3.6") (pin "1") (pinfunction "1_1") (pintype "passive"))
    )
    (net (code "69") (name "unconnected-(TEENSY 3.6-Pad2)") (class "Default")
      (node (ref "TEENSY 3.6") (pin "2") (pinfunction "2_2") (pintype "passive"))
    )
    (net (code "70") (name "unconnected-(TEENSY 3.6-Pad5)") (class "Default")
      (node (ref "TEENSY 3.6") (pin "5") (pinfunction "5_5") (pintype "passive"))
    )
    (net (code "71") (name "unconnected-(TEENSY 3.6-Pad6)") (class "Default")
      (node (ref "TEENSY 3.6") (pin "6") (pinfunction "6_6") (pintype "passive"))
    )
    (net (code "72") (name "unconnected-(TEENSY 3.6-Pad9)") (class "Default")
      (node (ref "TEENSY 3.6") (pin "9") (pinfunction "9_9") (pintype "passive"))
    )
    (net (code "73") (name "unconnected-(TEENSY 3.6-Pad10)") (class "Default")
      (node (ref "TEENSY 3.6") (pin "10") (pinfunction "10_10") (pintype "passive"))
    )
    (net (code "74") (name "unconnected-(TEENSY 3.6-Pad11)") (class "Default")
      (node (ref "TEENSY 3.6") (pin "11") (pinfunction "11_11") (pintype "passive"))
    )
    (net (code "75") (name "unconnected-(TEENSY 3.6-Pad12)") (class "Default")
      (node (ref "TEENSY 3.6") (pin "12") (pinfunction "12_12") (pintype "passive"))
    )
    (net (code "76") (name "unconnected-(TEENSY 3.6-Pad19)") (class "Default")
      (node (ref "TEENSY 3.6") (pin "19") (pinfunction "19_19") (pintype "passive"))
    )
    (net (code "77") (name "unconnected-(TEENSY 3.6-Pad24)") (class "Default")
      (node (ref "TEENSY 3.6") (pin "24") (pinfunction "24_24") (pintype "passive"))
    )
    (net (code "78") (name "unconnected-(TEENSY 3.6-Pad25)") (class "Default")
      (node (ref "TEENSY 3.6") (pin "25") (pinfunction "25_25") (pintype "passive"))
    )
    (net (code "79") (name "unconnected-(TEENSY 3.6-Pad26)") (class "Default")
      (node (ref "TEENSY 3.6") (pin "26") (pinfunction "26_26") (pintype "passive"))
    )
    (net (code "80") (name "unconnected-(TEENSY 3.6-Pad27)") (class "Default")
      (node (ref "TEENSY 3.6") (pin "27") (pinfunction "27_27") (pintype "passive"))
    )
    (net (code "81") (name "unconnected-(TEENSY 3.6-Pad28)") (class "Default")
      (node (ref "TEENSY 3.6") (pin "28") (pinfunction "28_28") (pintype "passive"))
    )
    (net (code "82") (name "unconnected-(TEENSY 3.6-Pad29)") (class "Default")
      (node (ref "TEENSY 3.6") (pin "29") (pinfunction "29_29") (pintype "passive"))
    )
    (net (code "83") (name "unconnected-(TEENSY 3.6-Pad30)") (class "Default")
      (node (ref "TEENSY 3.6") (pin "30") (pinfunction "30_30") (pintype "passive"))
    )
    (net (code "84") (name "unconnected-(TEENSY 3.6-Pad31)") (class "Default")
      (node (ref "TEENSY 3.6") (pin "31") (pinfunction "31_31") (pintype "passive"))
    )
    (net (code "85") (name "unconnected-(TEENSY 3.6-Pad32)") (class "Default")
      (node (ref "TEENSY 3.6") (pin "32") (pinfunction "32_32") (pintype "passive"))
    )
    (net (code "86") (name "unconnected-(TEENSY 3.6-Pad35)") (class "Default")
      (node (ref "TEENSY 3.6") (pin "35") (pinfunction "35_35") (pintype "passive"))
    )
    (net (code "87") (name "unconnected-(TEENSY 3.6-Pad36)") (class "Default")
      (node (ref "TEENSY 3.6") (pin "36") (pinfunction "36_36") (pintype "passive"))
    )
    (net (code "88") (name "unconnected-(TEENSY 3.6-Pad37)") (class "Default")
      (node (ref "TEENSY 3.6") (pin "37") (pinfunction "37_37") (pintype "passive"))
    )
    (net (code "89") (name "unconnected-(TEENSY 3.6-Pad38)") (class "Default")
      (node (ref "TEENSY 3.6") (pin "38") (pinfunction "38_38") (pintype "passive"))
    )
    (net (code "90") (name "unconnected-(TEENSY 3.6-Pad39)") (class "Default")
      (node (ref "TEENSY 3.6") (pin "39") (pinfunction "39_39") (pintype "passive"))
    )
    (net (code "91") (name "unconnected-(TEENSY 3.6-PadA21)") (class "Default")
      (node (ref "TEENSY 3.6") (pin "A21") (pinfunction "A21_A21") (pintype "passive"))
    )
    (net (code "92") (name "unconnected-(TEENSY 3.6-PadA22)") (class "Default")
      (node (ref "TEENSY 3.6") (pin "A22") (pinfunction "A22_A22") (pintype "passive"))
    )
    (net (code "93") (name "unconnected-(TEENSY 3.6-PadAREF)") (class "Default")
      (node (ref "TEENSY 3.6") (pin "AREF") (pinfunction "AREF_AREF") (pintype "passive"))
    )
    (net (code "94") (name "unconnected-(TEENSY 3.6-PadPROGRAM)") (class "Default")
      (node (ref "TEENSY 3.6") (pin "PROGRAM") (pinfunction "PROGRAM_PROGRAM") (pintype "passive"))
    )
    (net (code "95") (name "unconnected-(TEENSY 3.6-PadVBAT)") (class "Default")
      (node (ref "TEENSY 3.6") (pin "VBAT") (pinfunction "VBAT_VBAT") (pintype "passive"))
    )
    (net (code "96") (name "unconnected-(TEENSY 3.6-PadVUSB)") (class "Default")
      (node (ref "TEENSY 3.6") (pin "VUSB") (pinfunction "VUSB_VUSB") (pintype "passive"))
    )
    (net (code "97") (name "unconnected-(U2-Vref-Pad5)") (class "Default")
      (node (ref "U2") (pin "5") (pinfunction "Vref_5") (pintype "passive+no_connect"))
    )
    (net (code "98") (name "unconnected-(U3-DI8{slash}SLEEP_RQ{slash}DTR-Pad9)") (class "Default")
      (node (ref "U3") (pin "9") (pinfunction "DI8/SLEEP_RQ/DTR_9") (pintype "passive+no_connect"))
    )
    (net (code "99") (name "unconnected-(U3-DIO0{slash}AD0-Pad20)") (class "Default")
      (node (ref "U3") (pin "20") (pinfunction "DIO0/AD0_20") (pintype "passive+no_connect"))
    )
    (net (code "100") (name "unconnected-(U3-DIO1{slash}AD1{slash}SPI_ATTN-Pad19)") (class "Default")
      (node (ref "U3") (pin "19") (pinfunction "DIO1/AD1/SPI_ATTN_19") (pintype "passive+no_connect"))
    )
    (net (code "101") (name "unconnected-(U3-DIO2{slash}AD2{slash}SPI_CLK-Pad18)") (class "Default")
      (node (ref "U3") (pin "18") (pinfunction "DIO2/AD2/SPI_CLK_18") (pintype "passive+no_connect"))
    )
    (net (code "102") (name "unconnected-(U3-DIO3{slash}AD3{slash}SPI_SSEL-Pad17)") (class "Default")
      (node (ref "U3") (pin "17") (pinfunction "DIO3/AD3/SPI_SSEL_17") (pintype "passive+no_connect"))
    )
    (net (code "103") (name "unconnected-(U3-DIO4{slash}SPI_MOSI-Pad11)") (class "Default")
      (node (ref "U3") (pin "11") (pinfunction "DIO4/SPI_MOSI_11") (pintype "passive+no_connect"))
    )
    (net (code "104") (name "unconnected-(U3-DIO5{slash}ASSOC-Pad15)") (class "Default")
      (node (ref "U3") (pin "15") (pinfunction "DIO5/ASSOC_15") (pintype "passive+no_connect"))
    )
    (net (code "105") (name "unconnected-(U3-DIO6{slash}RTS-Pad16)") (class "Default")
      (node (ref "U3") (pin "16") (pinfunction "DIO6/RTS_16") (pintype "passive+no_connect"))
    )
    (net (code "106") (name "unconnected-(U3-DIO7{slash}CTS-Pad12)") (class "Default")
      (node (ref "U3") (pin "12") (pinfunction "DIO7/CTS_12") (pintype "passive+no_connect"))
    )
    (net (code "107") (name "unconnected-(U3-NC-Pad8)") (class "Default")
      (node (ref "U3") (pin "8") (pinfunction "NC_8") (pintype "passive+no_connect"))
    )
    (net (code "108") (name "unconnected-(U3-ON{slash}SLEEP-Pad13)") (class "Default")
      (node (ref "U3") (pin "13") (pinfunction "ON/SLEEP_13") (pintype "passive+no_connect"))
    )
    (net (code "109") (name "unconnected-(U3-PWM0{slash}RSSI-Pad6)") (class "Default")
      (node (ref "U3") (pin "6") (pinfunction "PWM0/RSSI_6") (pintype "passive+no_connect"))
    )
    (net (code "110") (name "unconnected-(U3-PWM1-Pad7)") (class "Default")
      (node (ref "U3") (pin "7") (pinfunction "PWM1_7") (pintype "passive+no_connect"))
    )
    (net (code "111") (name "unconnected-(U3-RESET-Pad5)") (class "Default")
      (node (ref "U3") (pin "5") (pinfunction "RESET_5") (pintype "passive+no_connect"))
    )
    (net (code "112") (name "unconnected-(U3-SPI_MISO-Pad4)") (class "Default")
      (node (ref "U3") (pin "4") (pinfunction "SPI_MISO_4") (pintype "passive+no_connect"))
    )
    (net (code "113") (name "unconnected-(U3-Vref-Pad14)") (class "Default")
      (node (ref "U3") (pin "14") (pinfunction "Vref_14") (pintype "passive+no_connect"))
    )
    (net (code "114") (name "unconnected-(U4-Vref-Pad5)") (class "Default")
      (node (ref "U4") (pin "5") (pinfunction "Vref_5") (pintype "passive+no_connect"))
    )
  )
)
